# rotarydial.net
KiCad netlist of a schematic drawn in EAGLE
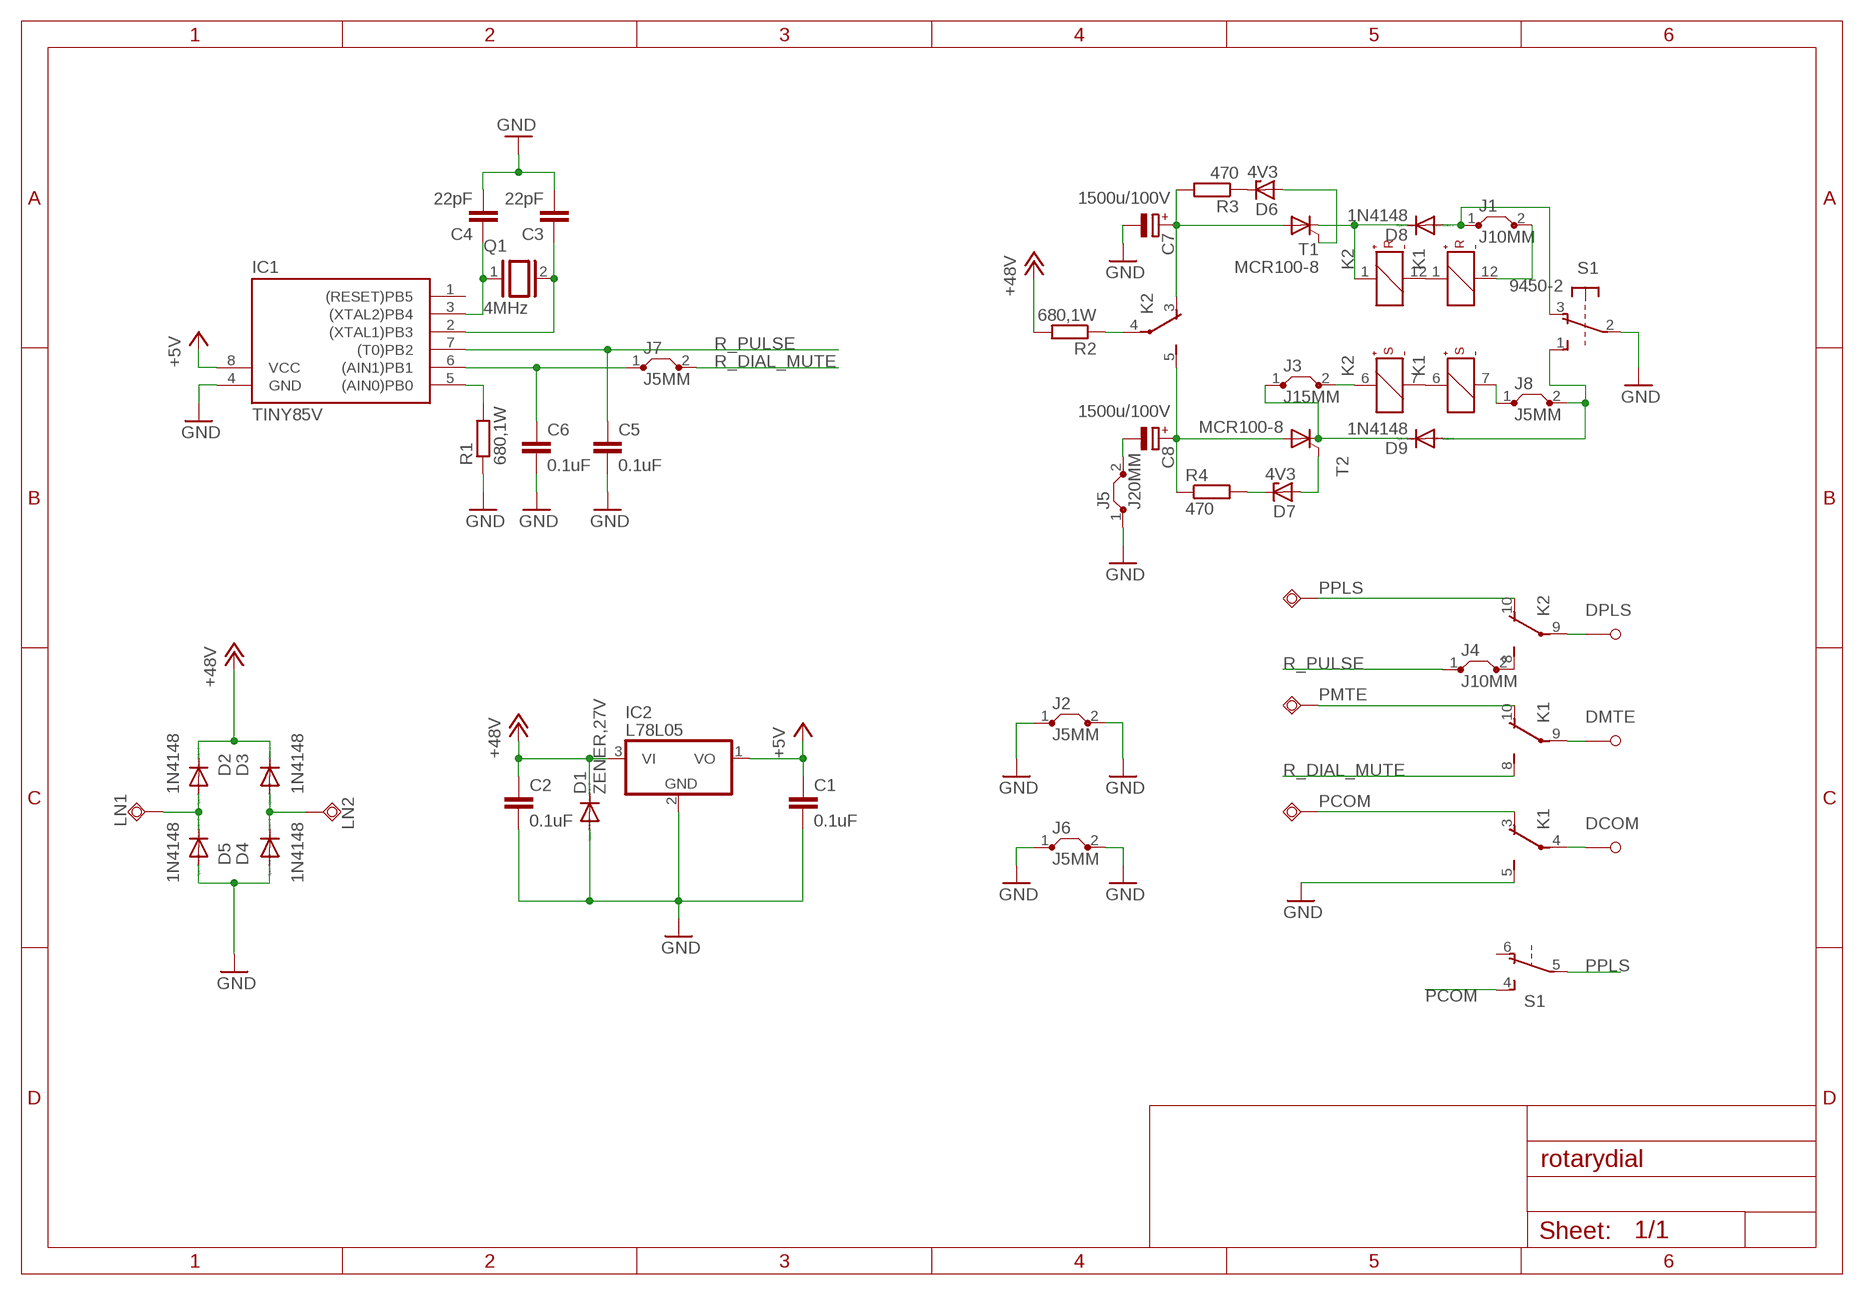
[diagram p0: schematic, sheet 1]

(export (version "E")
  (design (tool "Eeschema 10.0.6"))
  (components
    (comp (ref "C1")
      (value "0.1uF")
      (footprint "eagle-import:C050-025X075")
      (libsource (lib "eagle-import") (part "C-EU050-025X075"))
    )
    (comp (ref "C2")
      (value "0.1uF")
      (footprint "eagle-import:C050-025X075")
      (libsource (lib "eagle-import") (part "C-EU050-025X075"))
    )
    (comp (ref "C3")
      (value "22pF")
      (footprint "eagle-import:C050-024X044")
      (libsource (lib "eagle-import") (part "C-EU050-024X044"))
    )
    (comp (ref "C4")
      (value "22pF")
      (footprint "eagle-import:C050-024X044")
      (libsource (lib "eagle-import") (part "C-EU050-024X044"))
    )
    (comp (ref "C5")
      (value "0.1uF")
      (footprint "eagle-import:C050-025X075")
      (libsource (lib "eagle-import") (part "C-EU050-025X075"))
    )
    (comp (ref "C6")
      (value "0.1uF")
      (footprint "eagle-import:C050-025X075")
      (libsource (lib "eagle-import") (part "C-EU050-025X075"))
    )
    (comp (ref "C7")
      (value "1500u/100V")
      (footprint "eagle-import:E7,5-18")
      (libsource (lib "eagle-import") (part "CPOL-EUE7.5-18"))
    )
    (comp (ref "C8")
      (value "1500u/100V")
      (footprint "eagle-import:E7,5-18")
      (libsource (lib "eagle-import") (part "CPOL-EUE7.5-18"))
    )
    (comp (ref "D1")
      (value "ZENER,27V")
      (footprint "eagle-import:P2-15")
      (libsource (lib "eagle-import") (part "DIODE-P2-15"))
    )
    (comp (ref "D2")
      (value "1N4148")
      (footprint "eagle-import:DO41-10")
      (libsource (lib "eagle-import") (part "1N4933"))
    )
    (comp (ref "D3")
      (value "1N4148")
      (footprint "eagle-import:DO41-10")
      (libsource (lib "eagle-import") (part "1N4933"))
    )
    (comp (ref "D4")
      (value "1N4148")
      (footprint "eagle-import:DO41-10")
      (libsource (lib "eagle-import") (part "1N4933"))
    )
    (comp (ref "D5")
      (value "1N4148")
      (footprint "eagle-import:DO41-10")
      (libsource (lib "eagle-import") (part "1N4933"))
    )
    (comp (ref "D6")
      (value "4V3")
      (footprint "eagle-import:DO34Z7")
      (libsource (lib "eagle-import") (part "BZV10"))
    )
    (comp (ref "D7")
      (value "4V3")
      (footprint "eagle-import:DO34Z7")
      (libsource (lib "eagle-import") (part "BZV10"))
    )
    (comp (ref "D8")
      (value "1N4148")
      (footprint "eagle-import:DO41-10")
      (libsource (lib "eagle-import") (part "1N4933"))
    )
    (comp (ref "D9")
      (value "1N4148")
      (footprint "eagle-import:DO41-10")
      (libsource (lib "eagle-import") (part "1N4933"))
    )
    (comp (ref "DCOM")
      (value "M3-SCREW-CONNECTOR")
      (footprint "eagle-import:M3-SCREW-CONNECTOR")
      (libsource (lib "eagle-import") (part "M3-SCREW-CONNECTOR"))
    )
    (comp (ref "DMTE")
      (value "M3-SCREW-CONNECTOR")
      (footprint "eagle-import:M3-SCREW-CONNECTOR")
      (libsource (lib "eagle-import") (part "M3-SCREW-CONNECTOR"))
    )
    (comp (ref "DPLS")
      (value "M3-SCREW-CONNECTOR")
      (footprint "eagle-import:M3-SCREW-CONNECTOR")
      (libsource (lib "eagle-import") (part "M3-SCREW-CONNECTOR"))
    )
    (comp (ref "IC1")
      (value "TINY85V")
      (footprint "eagle-import:DIL08")
      (libsource (lib "eagle-import") (part "TINY10P"))
    )
    (comp (ref "IC2")
      (value "L78L05")
      (footprint "eagle-import:TO92")
      (libsource (lib "eagle-import") (part "78ZL05"))
    )
    (comp (ref "J1")
      (value "J10MM")
      (footprint "eagle-import:10")
      (libsource (lib "eagle-import") (part "J10MM"))
    )
    (comp (ref "J2")
      (value "J5MM")
      (footprint "eagle-import:05")
      (libsource (lib "eagle-import") (part "J5MM"))
    )
    (comp (ref "J3")
      (value "J15MM")
      (footprint "eagle-import:15")
      (libsource (lib "eagle-import") (part "J15MM"))
    )
    (comp (ref "J4")
      (value "J10MM")
      (footprint "eagle-import:10")
      (libsource (lib "eagle-import") (part "J10MM"))
    )
    (comp (ref "J5")
      (value "J20MM")
      (footprint "eagle-import:20")
      (libsource (lib "eagle-import") (part "J20MM"))
    )
    (comp (ref "J6")
      (value "J5MM")
      (footprint "eagle-import:05")
      (libsource (lib "eagle-import") (part "J5MM"))
    )
    (comp (ref "J7")
      (value "J5MM")
      (footprint "eagle-import:05")
      (libsource (lib "eagle-import") (part "J5MM"))
    )
    (comp (ref "J8")
      (value "J5MM")
      (footprint "eagle-import:05")
      (libsource (lib "eagle-import") (part "J5MM"))
    )
    (comp (ref "K1")
      (value "EC2-3TNU")
      (footprint "eagle-import:TX2-L2")
      (libsource (lib "eagle-import") (part "TX2?-L2-LT"))
    )
    (comp (ref "K2")
      (value "EC2-3TNU")
      (footprint "eagle-import:TX2-L2")
      (libsource (lib "eagle-import") (part "TX2?-L2-LT"))
    )
    (comp (ref "LN1")
      (value "TPSQPAD1-20")
      (footprint "eagle-import:P1-20")
      (libsource (lib "eagle-import") (part "TPSQPAD1-20"))
    )
    (comp (ref "LN2")
      (value "TPSQPAD1-20")
      (footprint "eagle-import:P1-20")
      (libsource (lib "eagle-import") (part "TPSQPAD1-20"))
    )
    (comp (ref "PCOM")
      (value "TPSQPAD1-20")
      (footprint "eagle-import:P1-20")
      (libsource (lib "eagle-import") (part "TPSQPAD1-20"))
    )
    (comp (ref "PMTE")
      (value "TPSQPAD1-20")
      (footprint "eagle-import:P1-20")
      (libsource (lib "eagle-import") (part "TPSQPAD1-20"))
    )
    (comp (ref "PPLS")
      (value "TPSQPAD1-20")
      (footprint "eagle-import:P1-20")
      (libsource (lib "eagle-import") (part "TPSQPAD1-20"))
    )
    (comp (ref "Q1")
      (value "4MHz")
      (footprint "eagle-import:QS")
      (libsource (lib "eagle-import") (part "XTAL/S"))
    )
    (comp (ref "R1")
      (value "680,1W")
      (footprint "eagle-import:0414V")
      (libsource (lib "eagle-import") (part "R-EU_0414/5V"))
    )
    (comp (ref "R2")
      (value "680,1W")
      (footprint "eagle-import:0414V")
      (libsource (lib "eagle-import") (part "R-EU_0414/5V"))
    )
    (comp (ref "R3")
      (value "470")
      (footprint "eagle-import:0207_7")
      (libsource (lib "eagle-import") (part "R-EU_0207/7"))
    )
    (comp (ref "R4")
      (value "470")
      (footprint "eagle-import:0207_7")
      (libsource (lib "eagle-import") (part "R-EU_0207/7"))
    )
    (comp (ref "S1")
      (value "9450-2")
      (footprint "eagle-import:9450-2")
      (libsource (lib "eagle-import") (part "9450-2"))
    )
    (comp (ref "T1")
      (value "MCR100-8")
      (footprint "eagle-import:TO92-2")
      (libsource (lib "eagle-import") (part "BT169"))
    )
    (comp (ref "T2")
      (value "MCR100-8")
      (footprint "eagle-import:TO92-2")
      (libsource (lib "eagle-import") (part "BT169"))
    )
  )
  (nets
    (net (code "1") (name "+5V") (class "Default")
      (node (ref "C1") (pin "1") (pinfunction "1_1") (pintype "passive"))
      (node (ref "IC1") (pin "8") (pinfunction "VCC_8") (pintype "power_in"))
      (node (ref "IC2") (pin "1") (pinfunction "VO_1") (pintype "passive"))
    )
    (net (code "2") (name "+48V") (class "Default")
      (node (ref "C2") (pin "1") (pinfunction "1_1") (pintype "passive"))
      (node (ref "D1") (pin "C") (pinfunction "C_C") (pintype "passive"))
      (node (ref "D2") (pin "C") (pinfunction "C_C") (pintype "passive"))
      (node (ref "D3") (pin "C") (pinfunction "C_C") (pintype "passive"))
      (node (ref "IC2") (pin "3") (pinfunction "VI_3") (pintype "input"))
      (node (ref "R2") (pin "2") (pinfunction "2_2") (pintype "passive"))
    )
    (net (code "3") (name "/PCOM") (class "Default")
      (node (ref "K1") (pin "3") (pinfunction "O_3") (pintype "passive"))
      (node (ref "PCOM") (pin "TP") (pinfunction "TP_TP") (pintype "input"))
      (node (ref "S1") (pin "4") (pinfunction "S_4") (pintype "passive"))
    )
    (net (code "4") (name "/PPLS") (class "Default")
      (node (ref "K2") (pin "10") (pinfunction "O_10") (pintype "passive"))
      (node (ref "PPLS") (pin "TP") (pinfunction "TP_TP") (pintype "input"))
      (node (ref "S1") (pin "5") (pinfunction "P_5") (pintype "passive"))
    )
    (net (code "5") (name "/R_DIAL_MUTE") (class "Default")
      (node (ref "C6") (pin "1") (pinfunction "1_1") (pintype "passive"))
      (node (ref "IC1") (pin "6") (pinfunction "(AIN1)PB1_6") (pintype "bidirectional"))
      (node (ref "J7") (pin "1") (pinfunction "1_1") (pintype "passive"))
      (node (ref "J7") (pin "2") (pinfunction "2_2") (pintype "passive"))
      (node (ref "K1") (pin "8") (pinfunction "S_8") (pintype "passive"))
    )
    (net (code "6") (name "/R_PULSE") (class "Default")
      (node (ref "C5") (pin "1") (pinfunction "1_1") (pintype "passive"))
      (node (ref "IC1") (pin "7") (pinfunction "(T0)PB2_7") (pintype "bidirectional"))
      (node (ref "J4") (pin "1") (pinfunction "1_1") (pintype "passive"))
    )
    (net (code "7") (name "GND") (class "Default")
      (node (ref "C1") (pin "2") (pinfunction "2_2") (pintype "passive"))
      (node (ref "C2") (pin "2") (pinfunction "2_2") (pintype "passive"))
      (node (ref "C3") (pin "2") (pinfunction "2_2") (pintype "passive"))
      (node (ref "C4") (pin "2") (pinfunction "2_2") (pintype "passive"))
      (node (ref "C5") (pin "2") (pinfunction "2_2") (pintype "passive"))
      (node (ref "C6") (pin "2") (pinfunction "2_2") (pintype "passive"))
      (node (ref "C7") (pin "-") (pinfunction "-_-") (pintype "passive"))
      (node (ref "C8") (pin "-") (pinfunction "-_-") (pintype "passive"))
      (node (ref "D1") (pin "A") (pinfunction "A_A") (pintype "passive"))
      (node (ref "D4") (pin "A") (pinfunction "A_A") (pintype "passive"))
      (node (ref "D5") (pin "A") (pinfunction "A_A") (pintype "passive"))
      (node (ref "IC1") (pin "4") (pinfunction "GND_4") (pintype "power_in"))
      (node (ref "IC2") (pin "2") (pinfunction "GND_2") (pintype "passive"))
      (node (ref "J2") (pin "1") (pinfunction "1_1") (pintype "passive"))
      (node (ref "J2") (pin "2") (pinfunction "2_2") (pintype "passive"))
      (node (ref "J5") (pin "1") (pinfunction "1_1") (pintype "passive"))
      (node (ref "J5") (pin "2") (pinfunction "2_2") (pintype "passive"))
      (node (ref "J6") (pin "1") (pinfunction "1_1") (pintype "passive"))
      (node (ref "J6") (pin "2") (pinfunction "2_2") (pintype "passive"))
      (node (ref "K1") (pin "5") (pinfunction "S_5") (pintype "passive"))
      (node (ref "R1") (pin "1") (pinfunction "1_1") (pintype "passive"))
      (node (ref "S1") (pin "2") (pinfunction "P_2") (pintype "passive"))
    )
    (net (code "8") (name "Net-(D2-PadA)") (class "Default")
      (node (ref "D2") (pin "A") (pinfunction "A_A") (pintype "passive"))
      (node (ref "D5") (pin "C") (pinfunction "C_C") (pintype "passive"))
      (node (ref "LN1") (pin "TP") (pinfunction "TP_TP") (pintype "input"))
    )
    (net (code "9") (name "Net-(D3-PadA)") (class "Default")
      (node (ref "D3") (pin "A") (pinfunction "A_A") (pintype "passive"))
      (node (ref "D4") (pin "C") (pinfunction "C_C") (pintype "passive"))
      (node (ref "LN2") (pin "TP") (pinfunction "TP_TP") (pintype "input"))
    )
    (net (code "10") (name "Net-(D6-PadA)") (class "Default")
      (node (ref "D6") (pin "A") (pinfunction "A_A") (pintype "passive"))
      (node (ref "T1") (pin "G") (pinfunction "G_G") (pintype "passive"))
    )
    (net (code "11") (name "Net-(D6-PadC)") (class "Default")
      (node (ref "D6") (pin "C") (pinfunction "C_C") (pintype "passive"))
      (node (ref "R3") (pin "1") (pinfunction "1_1") (pintype "passive"))
    )
    (net (code "12") (name "Net-(D7-PadA)") (class "Default")
      (node (ref "D7") (pin "A") (pinfunction "A_A") (pintype "passive"))
      (node (ref "T2") (pin "G") (pinfunction "G_G") (pintype "passive"))
    )
    (net (code "13") (name "Net-(D7-PadC)") (class "Default")
      (node (ref "D7") (pin "C") (pinfunction "C_C") (pintype "passive"))
      (node (ref "R4") (pin "2") (pinfunction "2_2") (pintype "passive"))
    )
    (net (code "14") (name "Net-(D9-PadC)") (class "Default")
      (node (ref "D9") (pin "C") (pinfunction "C_C") (pintype "passive"))
      (node (ref "J3") (pin "1") (pinfunction "1_1") (pintype "passive"))
      (node (ref "T2") (pin "C") (pinfunction "C_C") (pintype "passive"))
    )
    (net (code "15") (name "Net-(IC1-(AIN0)PB0)") (class "Default")
      (node (ref "IC1") (pin "5") (pinfunction "(AIN0)PB0_5") (pintype "bidirectional"))
      (node (ref "R1") (pin "2") (pinfunction "2_2") (pintype "passive"))
    )
    (net (code "16") (name "Net-(IC1-(XTAL1)PB3)") (class "Default")
      (node (ref "C3") (pin "1") (pinfunction "1_1") (pintype "passive"))
      (node (ref "IC1") (pin "2") (pinfunction "(XTAL1)PB3_2") (pintype "bidirectional"))
      (node (ref "Q1") (pin "2") (pinfunction "2_2") (pintype "passive"))
    )
    (net (code "17") (name "Net-(IC1-(XTAL2)PB4)") (class "Default")
      (node (ref "C4") (pin "1") (pinfunction "1_1") (pintype "passive"))
      (node (ref "IC1") (pin "3") (pinfunction "(XTAL2)PB4_3") (pintype "bidirectional"))
      (node (ref "Q1") (pin "1") (pinfunction "1_1") (pintype "passive"))
    )
    (net (code "18") (name "Net-(K1A-P)") (class "Default")
      (node (ref "DCOM") (pin "P$1") (pinfunction "P$1_P$1") (pintype "bidirectional"))
      (node (ref "DCOM") (pin "P$2") (pinfunction "P$1_P$2") (pintype "bidirectional"))
      (node (ref "DCOM") (pin "P$3") (pinfunction "P$1_P$3") (pintype "bidirectional"))
      (node (ref "DCOM") (pin "P$4") (pinfunction "P$1_P$4") (pintype "bidirectional"))
      (node (ref "K1") (pin "4") (pinfunction "P_4") (pintype "passive"))
    )
    (net (code "19") (name "Net-(K1B-O)") (class "Default")
      (node (ref "K1") (pin "10") (pinfunction "O_10") (pintype "passive"))
      (node (ref "PMTE") (pin "TP") (pinfunction "TP_TP") (pintype "input"))
    )
    (net (code "20") (name "Net-(K1B-P)") (class "Default")
      (node (ref "DMTE") (pin "P$1") (pinfunction "P$1_P$1") (pintype "bidirectional"))
      (node (ref "DMTE") (pin "P$2") (pinfunction "P$1_P$2") (pintype "bidirectional"))
      (node (ref "DMTE") (pin "P$3") (pinfunction "P$1_P$3") (pintype "bidirectional"))
      (node (ref "DMTE") (pin "P$4") (pinfunction "P$1_P$4") (pintype "bidirectional"))
      (node (ref "K1") (pin "9") (pinfunction "P_9") (pintype "passive"))
    )
    (net (code "21") (name "Net-(K1C-+)") (class "Default")
      (node (ref "K1") (pin "1") (pinfunction "+_1") (pintype "passive"))
      (node (ref "K2") (pin "12") (pinfunction "-_12") (pintype "passive"))
    )
    (net (code "22") (name "Net-(K1C--)") (class "Default")
      (node (ref "J1") (pin "2") (pinfunction "2_2") (pintype "passive"))
      (node (ref "K1") (pin "12") (pinfunction "-_12") (pintype "passive"))
    )
    (net (code "23") (name "Net-(K1D-+)") (class "Default")
      (node (ref "K1") (pin "6") (pinfunction "+_6") (pintype "passive"))
      (node (ref "K2") (pin "7") (pinfunction "-_7") (pintype "passive"))
    )
    (net (code "24") (name "Net-(K1D--)") (class "Default")
      (node (ref "J8") (pin "1") (pinfunction "1_1") (pintype "passive"))
      (node (ref "K1") (pin "7") (pinfunction "-_7") (pintype "passive"))
    )
    (net (code "25") (name "Net-(K2A-O)") (class "Default")
      (node (ref "C7") (pin "+") (pinfunction "+_+") (pintype "passive"))
      (node (ref "K2") (pin "3") (pinfunction "O_3") (pintype "passive"))
      (node (ref "R3") (pin "2") (pinfunction "2_2") (pintype "passive"))
      (node (ref "T1") (pin "A") (pinfunction "A_A") (pintype "passive"))
    )
    (net (code "26") (name "Net-(K2A-P)") (class "Default")
      (node (ref "K2") (pin "4") (pinfunction "P_4") (pintype "passive"))
      (node (ref "R2") (pin "1") (pinfunction "1_1") (pintype "passive"))
    )
    (net (code "27") (name "Net-(K2A-S)") (class "Default")
      (node (ref "C8") (pin "+") (pinfunction "+_+") (pintype "passive"))
      (node (ref "K2") (pin "5") (pinfunction "S_5") (pintype "passive"))
      (node (ref "R4") (pin "1") (pinfunction "1_1") (pintype "passive"))
      (node (ref "T2") (pin "A") (pinfunction "A_A") (pintype "passive"))
    )
    (net (code "28") (name "Net-(K2B-P)") (class "Default")
      (node (ref "DPLS") (pin "P$1") (pinfunction "P$1_P$1") (pintype "bidirectional"))
      (node (ref "DPLS") (pin "P$2") (pinfunction "P$1_P$2") (pintype "bidirectional"))
      (node (ref "DPLS") (pin "P$3") (pinfunction "P$1_P$3") (pintype "bidirectional"))
      (node (ref "DPLS") (pin "P$4") (pinfunction "P$1_P$4") (pintype "bidirectional"))
      (node (ref "K2") (pin "9") (pinfunction "P_9") (pintype "passive"))
    )
    (net (code "29") (name "Net-(K2B-S)") (class "Default")
      (node (ref "J4") (pin "2") (pinfunction "2_2") (pintype "passive"))
      (node (ref "K2") (pin "8") (pinfunction "S_8") (pintype "passive"))
    )
    (net (code "30") (name "Net-(K2C-+)") (class "Default")
      (node (ref "D8") (pin "C") (pinfunction "C_C") (pintype "passive"))
      (node (ref "K2") (pin "1") (pinfunction "+_1") (pintype "passive"))
      (node (ref "T1") (pin "C") (pinfunction "C_C") (pintype "passive"))
    )
    (net (code "31") (name "Net-(K2D-+)") (class "Default")
      (node (ref "J3") (pin "2") (pinfunction "2_2") (pintype "passive"))
      (node (ref "K2") (pin "6") (pinfunction "+_6") (pintype "passive"))
    )
    (net (code "32") (name "Net-(S1A-O)") (class "Default")
      (node (ref "D8") (pin "A") (pinfunction "A_A") (pintype "passive"))
      (node (ref "J1") (pin "1") (pinfunction "1_1") (pintype "passive"))
      (node (ref "S1") (pin "3") (pinfunction "O_3") (pintype "passive"))
    )
    (net (code "33") (name "Net-(S1A-S)") (class "Default")
      (node (ref "D9") (pin "A") (pinfunction "A_A") (pintype "passive"))
      (node (ref "J8") (pin "2") (pinfunction "2_2") (pintype "passive"))
      (node (ref "S1") (pin "1") (pinfunction "S_1") (pintype "passive"))
    )
    (net (code "34") (name "unconnected-(IC1-(RESET)PB5-Pad1)") (class "Default")
      (node (ref "IC1") (pin "1") (pinfunction "(RESET)PB5_1") (pintype "bidirectional"))
    )
    (net (code "35") (name "unconnected-(S1B-O-Pad6)") (class "Default")
      (node (ref "S1") (pin "6") (pinfunction "O_6") (pintype "passive"))
    )
  )
)
